# SCH_555-Circuit_2025-03-19.net
KiCad netlist of a schematic drawn in EasyEDA
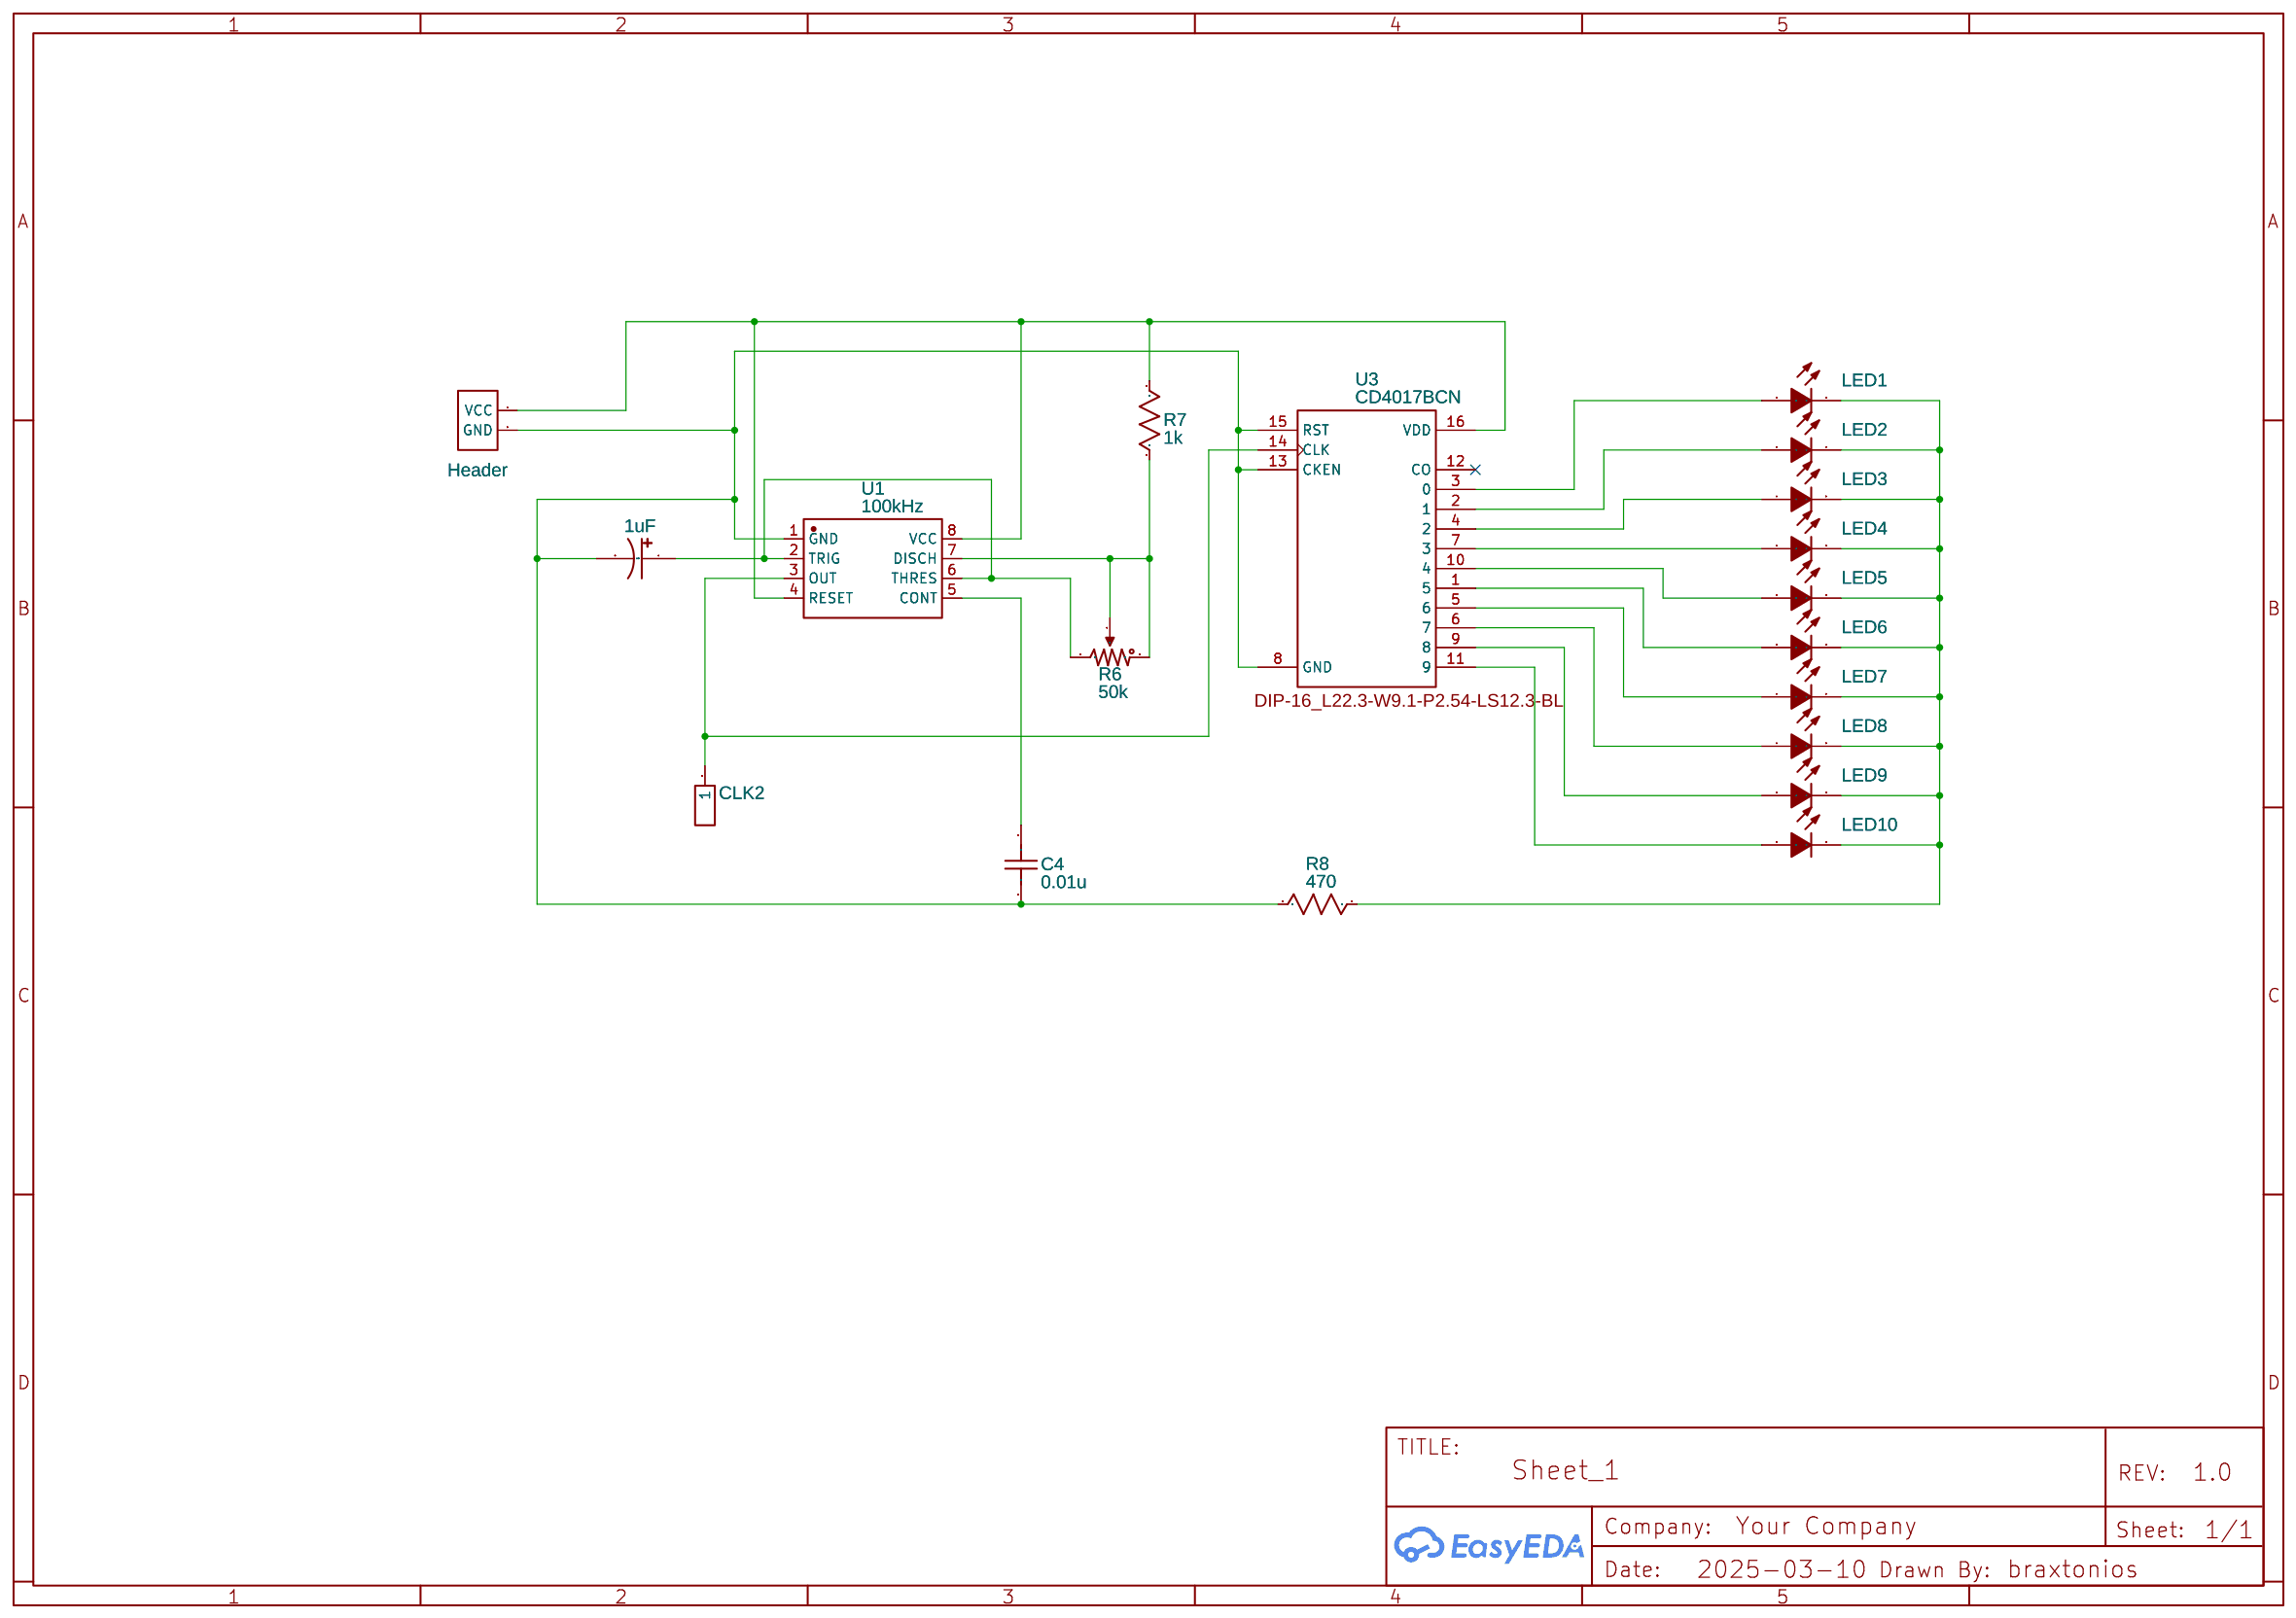
[diagram p0: schematic sheet]

(export (version "E")
  (design (tool "Eeschema 10.0.6"))
  (components
    (comp (ref "C3")
      (value "1uF")
      (fields (field (name "Manufacturer Part") "UVZ1H010MDD") (field (name "Manufacturer") "Nichicon(尼吉康)"))
      (libsource (lib "") (part "UVZ1H010MDD"))
    )
    (comp (ref "C4") (value "0.01u") (libsource (lib "") (part "C_0603_US")))
    (comp (ref "CLK2")
      (value "C81276")
      (fields
        (field (name "Manufacturer Part") "2.54-1*1P针")
        (field (name "Manufacturer") "BOOMELE(Boom Precision Elec)")
      )
      (libsource (lib "") (part "Header-Male-2.54_1x1"))
    )
    (comp (ref "H2") (value "Header") (libsource (lib "") (part "HEADER-FEMALE-2.54_1X2")))
    (comp (ref "LED1") (value "LED_5MM") (libsource (lib "") (part "LED_5MM")))
    (comp (ref "LED2") (value "LED_5MM") (libsource (lib "") (part "LED_5MM")))
    (comp (ref "LED3") (value "LED_5MM") (libsource (lib "") (part "LED_5MM")))
    (comp (ref "LED4") (value "LED_5MM") (libsource (lib "") (part "LED_5MM")))
    (comp (ref "LED5") (value "LED_5MM") (libsource (lib "") (part "LED_5MM")))
    (comp (ref "LED6") (value "LED_5MM") (libsource (lib "") (part "LED_5MM")))
    (comp (ref "LED7") (value "LED_5MM") (libsource (lib "") (part "LED_5MM")))
    (comp (ref "LED8") (value "LED_5MM") (libsource (lib "") (part "LED_5MM")))
    (comp (ref "LED9") (value "LED_5MM") (libsource (lib "") (part "LED_5MM")))
    (comp (ref "LED10") (value "LED_5MM") (libsource (lib "") (part "LED_5MM")))
    (comp (ref "R6")
      (value "50k")
      (fields (field (name "Manufacturer Part") "?"))
      (libsource (lib "") (part "Potentiometer"))
    )
    (comp (ref "R7")
      (value "1k")
      (fields (field (name "Manufacturer Part") "?"))
      (libsource (lib "") (part "Resistor"))
    )
    (comp (ref "R8")
      (value "470")
      (fields (field (name "Manufacturer Part") "?"))
      (libsource (lib "") (part "Resistor_1"))
    )
    (comp (ref "U1")
      (value "100kHz")
      (fields (field (name "Manufacturer Part") "NE555P") (field (name "Manufacturer") "TI(德州仪器)"))
      (libsource (lib "") (part "NE555P"))
    )
    (comp (ref "U3") (value "CD4017BCN") (libsource (lib "") (part "CD4017BCN")))
  )
  (nets
    (net (code "1") (name "Net-(H2-GND)") (class "Default")
      (node (ref "C3") (pin "2") (pinfunction "2_2") (pintype "unspecified"))
      (node (ref "C4") (pin "2") (pinfunction "2_2") (pintype "unspecified"))
      (node (ref "H2") (pin "2") (pinfunction "GND_2") (pintype "unspecified"))
      (node (ref "R8") (pin "2") (pinfunction "2_2") (pintype "unspecified"))
      (node (ref "U1") (pin "1") (pinfunction "GND_1") (pintype "unspecified"))
      (node (ref "U3") (pin "13") (pinfunction "CKEN_13") (pintype "unspecified"))
      (node (ref "U3") (pin "15") (pinfunction "RST_15") (pintype "unspecified"))
      (node (ref "U3") (pin "8") (pinfunction "GND_8") (pintype "passive"))
    )
    (net (code "2") (name "Net-(H2-VCC)") (class "Default")
      (node (ref "H2") (pin "1") (pinfunction "VCC_1") (pintype "unspecified"))
      (node (ref "R7") (pin "2") (pinfunction "2_2") (pintype "unspecified"))
      (node (ref "U1") (pin "4") (pinfunction "RESET_4") (pintype "unspecified"))
      (node (ref "U1") (pin "8") (pinfunction "VCC_8") (pintype "unspecified"))
      (node (ref "U3") (pin "16") (pinfunction "VDD_16") (pintype "passive"))
    )
    (net (code "3") (name "Net-(LED1-A)") (class "Default")
      (node (ref "LED1") (pin "1") (pinfunction "A_1") (pintype "input"))
      (node (ref "U3") (pin "3") (pinfunction "0_3") (pintype "output"))
    )
    (net (code "4") (name "Net-(LED1-K)") (class "Default")
      (node (ref "LED1") (pin "2") (pinfunction "K_2") (pintype "input"))
      (node (ref "LED10") (pin "2") (pinfunction "K_2") (pintype "input"))
      (node (ref "LED2") (pin "2") (pinfunction "K_2") (pintype "input"))
      (node (ref "LED3") (pin "2") (pinfunction "K_2") (pintype "input"))
      (node (ref "LED4") (pin "2") (pinfunction "K_2") (pintype "input"))
      (node (ref "LED5") (pin "2") (pinfunction "K_2") (pintype "input"))
      (node (ref "LED6") (pin "2") (pinfunction "K_2") (pintype "input"))
      (node (ref "LED7") (pin "2") (pinfunction "K_2") (pintype "input"))
      (node (ref "LED8") (pin "2") (pinfunction "K_2") (pintype "input"))
      (node (ref "LED9") (pin "2") (pinfunction "K_2") (pintype "input"))
      (node (ref "R8") (pin "1") (pinfunction "1_1") (pintype "unspecified"))
    )
    (net (code "5") (name "Net-(LED2-A)") (class "Default")
      (node (ref "LED2") (pin "1") (pinfunction "A_1") (pintype "input"))
      (node (ref "U3") (pin "2") (pinfunction "1_2") (pintype "output"))
    )
    (net (code "6") (name "Net-(LED3-A)") (class "Default")
      (node (ref "LED3") (pin "1") (pinfunction "A_1") (pintype "input"))
      (node (ref "U3") (pin "4") (pinfunction "2_4") (pintype "output"))
    )
    (net (code "7") (name "Net-(LED4-A)") (class "Default")
      (node (ref "LED4") (pin "1") (pinfunction "A_1") (pintype "input"))
      (node (ref "U3") (pin "7") (pinfunction "3_7") (pintype "output"))
    )
    (net (code "8") (name "Net-(LED5-A)") (class "Default")
      (node (ref "LED5") (pin "1") (pinfunction "A_1") (pintype "input"))
      (node (ref "U3") (pin "10") (pinfunction "4_10") (pintype "output"))
    )
    (net (code "9") (name "Net-(LED6-A)") (class "Default")
      (node (ref "LED6") (pin "1") (pinfunction "A_1") (pintype "input"))
      (node (ref "U3") (pin "1") (pinfunction "5_1") (pintype "output"))
    )
    (net (code "10") (name "Net-(LED7-A)") (class "Default")
      (node (ref "LED7") (pin "1") (pinfunction "A_1") (pintype "input"))
      (node (ref "U3") (pin "5") (pinfunction "6_5") (pintype "output"))
    )
    (net (code "11") (name "Net-(LED8-A)") (class "Default")
      (node (ref "LED8") (pin "1") (pinfunction "A_1") (pintype "input"))
      (node (ref "U3") (pin "6") (pinfunction "7_6") (pintype "output"))
    )
    (net (code "12") (name "Net-(LED9-A)") (class "Default")
      (node (ref "LED9") (pin "1") (pinfunction "A_1") (pintype "input"))
      (node (ref "U3") (pin "9") (pinfunction "8_9") (pintype "output"))
    )
    (net (code "13") (name "Net-(LED10-A)") (class "Default")
      (node (ref "LED10") (pin "1") (pinfunction "A_1") (pintype "input"))
      (node (ref "U3") (pin "11") (pinfunction "9_11") (pintype "output"))
    )
    (net (code "14") (name "Net-(R6-2)") (class "Default")
      (node (ref "R6") (pin "2") (pinfunction "3_2") (pintype "unspecified"))
      (node (ref "R6") (pin "3") (pinfunction "2_3") (pintype "unspecified"))
      (node (ref "R7") (pin "1") (pinfunction "1_1") (pintype "unspecified"))
      (node (ref "U1") (pin "7") (pinfunction "DISCH_7") (pintype "unspecified"))
    )
    (net (code "15") (name "Net-(U1-CONT)") (class "Default")
      (node (ref "C4") (pin "1") (pinfunction "1_1") (pintype "unspecified"))
      (node (ref "U1") (pin "5") (pinfunction "CONT_5") (pintype "unspecified"))
    )
    (net (code "16") (name "Net-(U1-OUT)") (class "Default")
      (node (ref "CLK2") (pin "1") (pinfunction "1_1") (pintype "unspecified"))
      (node (ref "U1") (pin "3") (pinfunction "OUT_3") (pintype "unspecified"))
      (node (ref "U3") (pin "14") (pinfunction "CLK_14") (pintype "unspecified"))
    )
    (net (code "17") (name "Net-(U1-THRES)") (class "Default")
      (node (ref "C3") (pin "1") (pinfunction "1_1") (pintype "unspecified"))
      (node (ref "R6") (pin "1") (pinfunction "1_1") (pintype "unspecified"))
      (node (ref "U1") (pin "2") (pinfunction "TRIG_2") (pintype "unspecified"))
      (node (ref "U1") (pin "6") (pinfunction "THRES_6") (pintype "unspecified"))
    )
    (net (code "18") (name "unconnected-(U3-CO-Pad12)") (class "Default")
      (node (ref "U3") (pin "12") (pinfunction "CO_12") (pintype "output+no_connect"))
    )
  )
)
